# MACS7.net
KiCad netlist of a schematic drawn in EAGLE
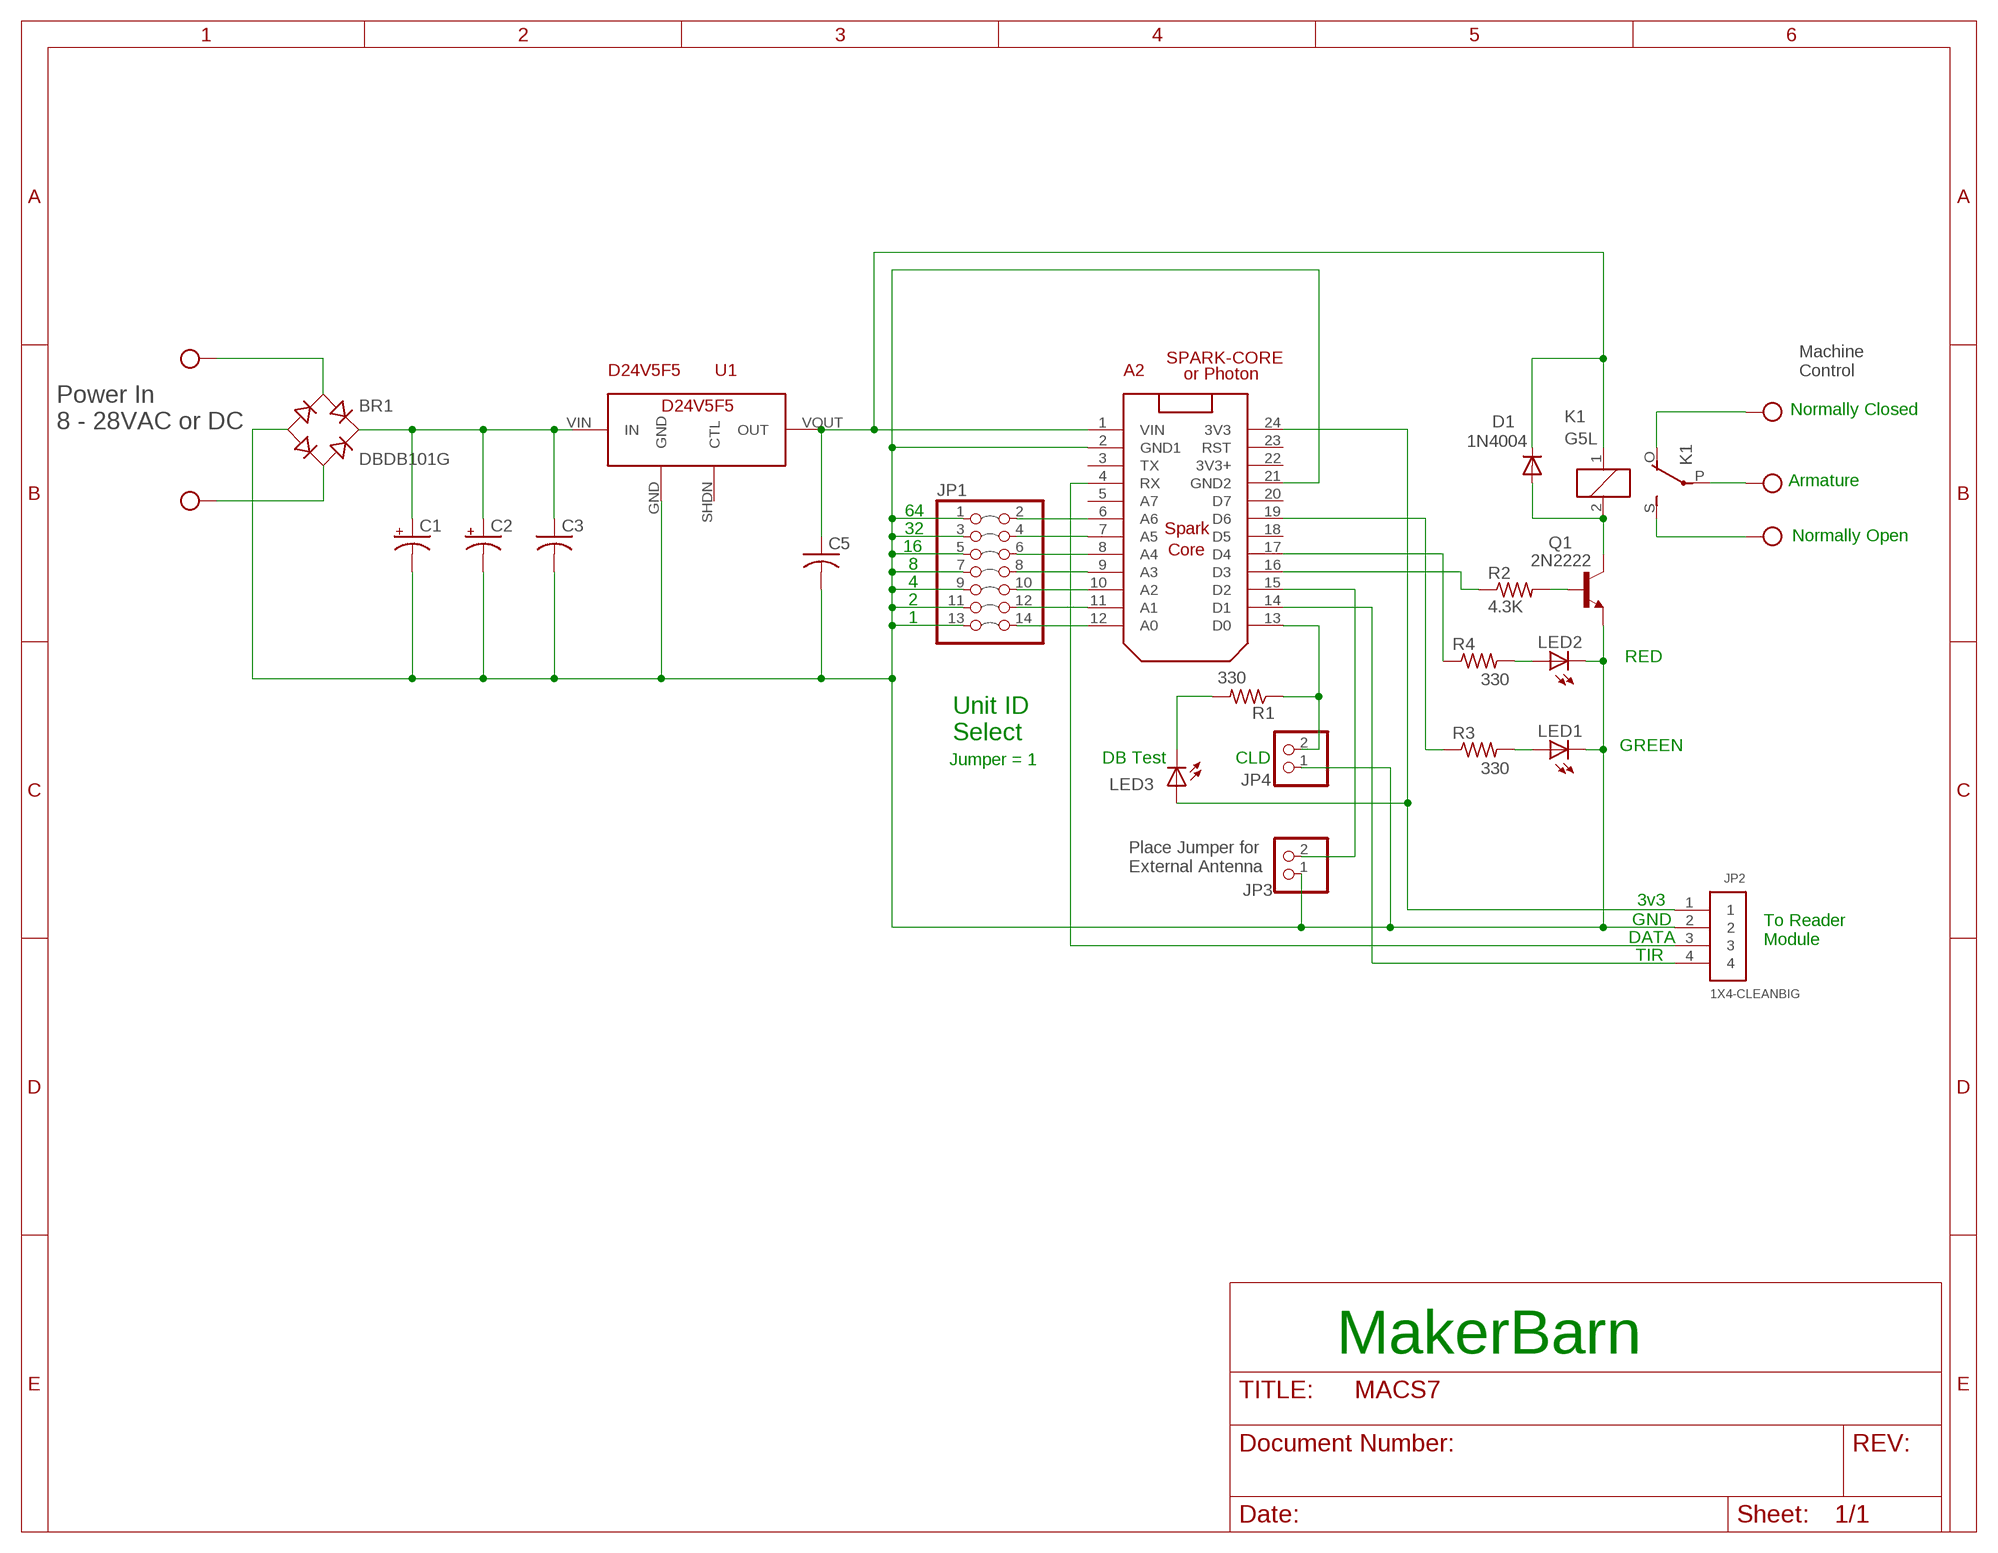
[diagram p0: schematic, sheet 1]

(export (version "E")
  (design (tool "Eeschema 10.0.6"))
  (components
    (comp (ref "A2")
      (value "SPARK-CORE")
      (footprint "eagle-import:SPARK-CORE")
      (libsource (lib "eagle-import") (part "SPARK-CORE"))
    )
    (comp (ref "BR1")
      (value "DBDB101G")
      (footprint "eagle-import:DB")
      (libsource (lib "eagle-import") (part "DB?GDB101"))
    )
    (comp (ref "C1")
      (value "CPOL-USE35-16AXIAL")
      (footprint "eagle-import:E35-16")
      (libsource (lib "eagle-import") (part "CPOL-USE35-16AXIAL"))
    )
    (comp (ref "C2")
      (value "CPOL-USE35-16AXIAL")
      (footprint "eagle-import:E35-16")
      (libsource (lib "eagle-import") (part "CPOL-USE35-16AXIAL"))
    )
    (comp (ref "C3")
      (value "C-US050-035X075")
      (footprint "eagle-import:C050-035X075")
      (libsource (lib "eagle-import") (part "C-US050-035X075"))
    )
    (comp (ref "C5")
      (value "C-US050-035X075")
      (footprint "eagle-import:C050-035X075")
      (libsource (lib "eagle-import") (part "C-US050-035X075"))
    )
    (comp (ref "D1")
      (value "1N4004")
      (footprint "eagle-import:DO41-10")
      (libsource (lib "eagle-import") (part "1N4004"))
    )
    (comp (ref "JP1")
      (value "PINHD-2X7")
      (footprint "eagle-import:2X07")
      (libsource (lib "eagle-import") (part "PINHD-2X7"))
    )
    (comp (ref "JP2")
      (value "1X4-CLEANBIG")
      (footprint "eagle-import:1X04-CLEANBIG")
      (libsource (lib "eagle-import") (part "1X4-CLEANBIG"))
    )
    (comp (ref "JP3")
      (value "PINHD-1X2")
      (footprint "eagle-import:1X02")
      (libsource (lib "eagle-import") (part "PINHD-1X2"))
    )
    (comp (ref "JP4")
      (value "PINHD-1X2")
      (footprint "eagle-import:1X02")
      (libsource (lib "eagle-import") (part "PINHD-1X2"))
    )
    (comp (ref "K1")
      (value "G5L")
      (footprint "eagle-import:G5LE")
      (libsource (lib "eagle-import") (part "G5L"))
    )
    (comp (ref "LED1")
      (value "LED5MM")
      (footprint "eagle-import:LED5MM")
      (libsource (lib "eagle-import") (part "led_LED5MM"))
    )
    (comp (ref "LED2")
      (value "LED5MM")
      (footprint "eagle-import:LED5MM")
      (libsource (lib "eagle-import") (part "led_LED5MM"))
    )
    (comp (ref "LED3")
      (value "LED3MM")
      (footprint "eagle-import:LED3MM")
      (libsource (lib "eagle-import") (part "LED3MM"))
    )
    (comp (ref "Q1")
      (value "2N2222")
      (footprint "eagle-import:TO92-EBC-OVAL")
      (libsource (lib "eagle-import") (part "2N2222"))
    )
    (comp (ref "R1")
      (value "330")
      (footprint "eagle-import:R0805")
      (libsource (lib "eagle-import") (part "R-US_R0805"))
    )
    (comp (ref "R2")
      (value "4.3K")
      (footprint "eagle-import:R0805")
      (libsource (lib "eagle-import") (part "R-US_R0805"))
    )
    (comp (ref "R3")
      (value "330")
      (footprint "eagle-import:R0805")
      (libsource (lib "eagle-import") (part "R-US_R0805"))
    )
    (comp (ref "R4")
      (value "330")
      (footprint "eagle-import:R0805")
      (libsource (lib "eagle-import") (part "R-US_R0805"))
    )
    (comp (ref "U1")
      (value "D24V5F5")
      (footprint "eagle-import:POLOLUREG")
      (libsource (lib "eagle-import") (part "D24V5F5"))
    )
    (comp (ref "X2")
      (value "MKDSN1,5/2-5,08")
      (footprint "eagle-import:MKDSN1,5_2-5,08")
      (libsource (lib "eagle-import") (part "MKDSN1,5/2-5,08"))
    )
    (comp (ref "X3")
      (value "MKDSN1,5/3-5,08")
      (footprint "eagle-import:MKDSN1,5_3-5,08")
      (libsource (lib "eagle-import") (part "MKDSN1,5/3-5,08"))
    )
  )
  (nets
    (net (code "1") (name "Net-(A2-3V3)") (class "Default")
      (node (ref "A2") (pin "24") (pinfunction "3V3_24") (pintype "bidirectional"))
      (node (ref "JP2") (pin "1") (pinfunction "1_1") (pintype "bidirectional"))
      (node (ref "LED3") (pin "A") (pinfunction "A_A") (pintype "passive"))
    )
    (net (code "2") (name "Net-(A2-A0)") (class "Default")
      (node (ref "A2") (pin "12") (pinfunction "A0_12") (pintype "bidirectional"))
      (node (ref "JP1") (pin "14") (pinfunction "14_14") (pintype "passive"))
    )
    (net (code "3") (name "Net-(A2-A1)") (class "Default")
      (node (ref "A2") (pin "11") (pinfunction "A1_11") (pintype "bidirectional"))
      (node (ref "JP1") (pin "12") (pinfunction "12_12") (pintype "passive"))
    )
    (net (code "4") (name "Net-(A2-A2)") (class "Default")
      (node (ref "A2") (pin "10") (pinfunction "A2_10") (pintype "bidirectional"))
      (node (ref "JP1") (pin "10") (pinfunction "10_10") (pintype "passive"))
    )
    (net (code "5") (name "Net-(A2-A3)") (class "Default")
      (node (ref "A2") (pin "9") (pinfunction "A3_9") (pintype "bidirectional"))
      (node (ref "JP1") (pin "8") (pinfunction "8_8") (pintype "passive"))
    )
    (net (code "6") (name "Net-(A2-A4)") (class "Default")
      (node (ref "A2") (pin "8") (pinfunction "A4_8") (pintype "bidirectional"))
      (node (ref "JP1") (pin "6") (pinfunction "6_6") (pintype "passive"))
    )
    (net (code "7") (name "Net-(A2-A5)") (class "Default")
      (node (ref "A2") (pin "7") (pinfunction "A5_7") (pintype "bidirectional"))
      (node (ref "JP1") (pin "4") (pinfunction "4_4") (pintype "passive"))
    )
    (net (code "8") (name "Net-(A2-A6)") (class "Default")
      (node (ref "A2") (pin "6") (pinfunction "A6_6") (pintype "bidirectional"))
      (node (ref "JP1") (pin "2") (pinfunction "2_2") (pintype "passive"))
    )
    (net (code "9") (name "Net-(A2-D0)") (class "Default")
      (node (ref "A2") (pin "13") (pinfunction "D0_13") (pintype "bidirectional"))
      (node (ref "JP4") (pin "2") (pinfunction "2_2") (pintype "passive"))
      (node (ref "R1") (pin "1") (pinfunction "1_1") (pintype "passive"))
    )
    (net (code "10") (name "Net-(A2-D1)") (class "Default")
      (node (ref "A2") (pin "14") (pinfunction "D1_14") (pintype "bidirectional"))
      (node (ref "JP2") (pin "4") (pinfunction "4_4") (pintype "bidirectional"))
    )
    (net (code "11") (name "Net-(A2-D2)") (class "Default")
      (node (ref "A2") (pin "15") (pinfunction "D2_15") (pintype "bidirectional"))
      (node (ref "JP3") (pin "2") (pinfunction "2_2") (pintype "passive"))
    )
    (net (code "12") (name "Net-(A2-D3)") (class "Default")
      (node (ref "A2") (pin "16") (pinfunction "D3_16") (pintype "bidirectional"))
      (node (ref "R2") (pin "1") (pinfunction "1_1") (pintype "passive"))
    )
    (net (code "13") (name "Net-(A2-D4)") (class "Default")
      (node (ref "A2") (pin "17") (pinfunction "D4_17") (pintype "bidirectional"))
      (node (ref "R4") (pin "1") (pinfunction "1_1") (pintype "passive"))
    )
    (net (code "14") (name "Net-(A2-D6)") (class "Default")
      (node (ref "A2") (pin "19") (pinfunction "D6_19") (pintype "bidirectional"))
      (node (ref "R3") (pin "1") (pinfunction "1_1") (pintype "passive"))
    )
    (net (code "15") (name "Net-(A2-GND1)") (class "Default")
      (node (ref "A2") (pin "2") (pinfunction "GND1_2") (pintype "power_in"))
      (node (ref "A2") (pin "21") (pinfunction "GND2_21") (pintype "power_in"))
      (node (ref "BR1") (pin "-") (pinfunction "-_-") (pintype "passive"))
      (node (ref "C1") (pin "-") (pinfunction "-_-") (pintype "passive"))
      (node (ref "C2") (pin "-") (pinfunction "-_-") (pintype "passive"))
      (node (ref "C3") (pin "2") (pinfunction "2_2") (pintype "passive"))
      (node (ref "C5") (pin "2") (pinfunction "2_2") (pintype "passive"))
      (node (ref "JP1") (pin "1") (pinfunction "1_1") (pintype "passive"))
      (node (ref "JP1") (pin "11") (pinfunction "11_11") (pintype "passive"))
      (node (ref "JP1") (pin "13") (pinfunction "13_13") (pintype "passive"))
      (node (ref "JP1") (pin "3") (pinfunction "3_3") (pintype "passive"))
      (node (ref "JP1") (pin "5") (pinfunction "5_5") (pintype "passive"))
      (node (ref "JP1") (pin "7") (pinfunction "7_7") (pintype "passive"))
      (node (ref "JP1") (pin "9") (pinfunction "9_9") (pintype "passive"))
      (node (ref "JP2") (pin "2") (pinfunction "2_2") (pintype "bidirectional"))
      (node (ref "JP3") (pin "1") (pinfunction "1_1") (pintype "passive"))
      (node (ref "JP4") (pin "1") (pinfunction "1_1") (pintype "passive"))
      (node (ref "LED1") (pin "K") (pinfunction "C_K") (pintype "passive"))
      (node (ref "LED2") (pin "K") (pinfunction "C_K") (pintype "passive"))
      (node (ref "Q1") (pin "E") (pinfunction "E_E") (pintype "passive"))
      (node (ref "U1") (pin "GND") (pinfunction "GND_GND") (pintype "bidirectional"))
    )
    (net (code "16") (name "Net-(A2-RX)") (class "Default")
      (node (ref "A2") (pin "4") (pinfunction "RX_4") (pintype "bidirectional"))
      (node (ref "JP2") (pin "3") (pinfunction "3_3") (pintype "bidirectional"))
    )
    (net (code "17") (name "Net-(A2-VIN)") (class "Default")
      (node (ref "A2") (pin "1") (pinfunction "VIN_1") (pintype "bidirectional"))
      (node (ref "C5") (pin "1") (pinfunction "1_1") (pintype "passive"))
      (node (ref "D1") (pin "C") (pinfunction "C_C") (pintype "passive"))
      (node (ref "K1") (pin "1") (pinfunction "1_1") (pintype "passive"))
      (node (ref "U1") (pin "VOUT") (pinfunction "OUT_VOUT") (pintype "bidirectional"))
    )
    (net (code "18") (name "Net-(D1-PadA)") (class "Default")
      (node (ref "D1") (pin "A") (pinfunction "A_A") (pintype "passive"))
      (node (ref "K1") (pin "2") (pinfunction "2_2") (pintype "passive"))
      (node (ref "Q1") (pin "C") (pinfunction "C_C") (pintype "passive"))
    )
    (net (code "19") (name "Net-(LED1-PadA)") (class "Default")
      (node (ref "LED1") (pin "A") (pinfunction "A_A") (pintype "passive"))
      (node (ref "R3") (pin "2") (pinfunction "2_2") (pintype "passive"))
    )
    (net (code "20") (name "Net-(LED2-PadA)") (class "Default")
      (node (ref "LED2") (pin "A") (pinfunction "A_A") (pintype "passive"))
      (node (ref "R4") (pin "2") (pinfunction "2_2") (pintype "passive"))
    )
    (net (code "21") (name "Net-(LED3-C)") (class "Default")
      (node (ref "LED3") (pin "K") (pinfunction "C_K") (pintype "passive"))
      (node (ref "R1") (pin "2") (pinfunction "2_2") (pintype "passive"))
    )
    (net (code "22") (name "Net-(Q1-PadB)") (class "Default")
      (node (ref "Q1") (pin "B") (pinfunction "B_B") (pintype "passive"))
      (node (ref "R2") (pin "2") (pinfunction "2_2") (pintype "passive"))
    )
    (net (code "23") (name "Net-(U1-IN)") (class "Default")
      (node (ref "BR1") (pin "+") (pinfunction "+_+") (pintype "passive"))
      (node (ref "C1") (pin "+") (pinfunction "+_+") (pintype "passive"))
      (node (ref "C2") (pin "+") (pinfunction "+_+") (pintype "passive"))
      (node (ref "C3") (pin "1") (pinfunction "1_1") (pintype "passive"))
      (node (ref "U1") (pin "VIN") (pinfunction "IN_VIN") (pintype "bidirectional"))
    )
    (net (code "24") (name "Net-(X2A-KL)") (class "Default")
      (node (ref "BR1") (pin "AC1") (pinfunction "AC1_AC1") (pintype "passive"))
      (node (ref "X2") (pin "1") (pinfunction "KL_1") (pintype "passive"))
    )
    (net (code "25") (name "Net-(X2B-KL)") (class "Default")
      (node (ref "BR1") (pin "AC2") (pinfunction "AC2_AC2") (pintype "passive"))
      (node (ref "X2") (pin "2") (pinfunction "KL_2") (pintype "passive"))
    )
    (net (code "26") (name "Net-(X3A-KL)") (class "Default")
      (node (ref "K1") (pin "P") (pinfunction "P_P") (pintype "passive"))
      (node (ref "X3") (pin "1") (pinfunction "KL_1") (pintype "passive"))
    )
    (net (code "27") (name "Net-(X3B-KL)") (class "Default")
      (node (ref "K1") (pin "O") (pinfunction "O_O") (pintype "passive"))
      (node (ref "X3") (pin "2") (pinfunction "KL_2") (pintype "passive"))
    )
    (net (code "28") (name "Net-(X3C-KL)") (class "Default")
      (node (ref "K1") (pin "S") (pinfunction "S_S") (pintype "passive"))
      (node (ref "X3") (pin "3") (pinfunction "KL_3") (pintype "passive"))
    )
    (net (code "29") (name "unconnected-(A2-3V3+-Pad22)") (class "Default")
      (node (ref "A2") (pin "22") (pinfunction "3V3+_22") (pintype "bidirectional"))
    )
    (net (code "30") (name "unconnected-(A2-A7-Pad5)") (class "Default")
      (node (ref "A2") (pin "5") (pinfunction "A7_5") (pintype "bidirectional"))
    )
    (net (code "31") (name "unconnected-(A2-D5-Pad18)") (class "Default")
      (node (ref "A2") (pin "18") (pinfunction "D5_18") (pintype "bidirectional"))
    )
    (net (code "32") (name "unconnected-(A2-D7-Pad20)") (class "Default")
      (node (ref "A2") (pin "20") (pinfunction "D7_20") (pintype "bidirectional"))
    )
    (net (code "33") (name "unconnected-(A2-RST-Pad23)") (class "Default")
      (node (ref "A2") (pin "23") (pinfunction "RST_23") (pintype "bidirectional"))
    )
    (net (code "34") (name "unconnected-(A2-TX-Pad3)") (class "Default")
      (node (ref "A2") (pin "3") (pinfunction "TX_3") (pintype "bidirectional"))
    )
    (net (code "35") (name "unconnected-(U1-CTL-PadSHDN)") (class "Default")
      (node (ref "U1") (pin "SHDN") (pinfunction "CTL_SHDN") (pintype "bidirectional"))
    )
  )
)
